# 5VProtect.net
KiCad netlist of a schematic drawn in Altium Designer
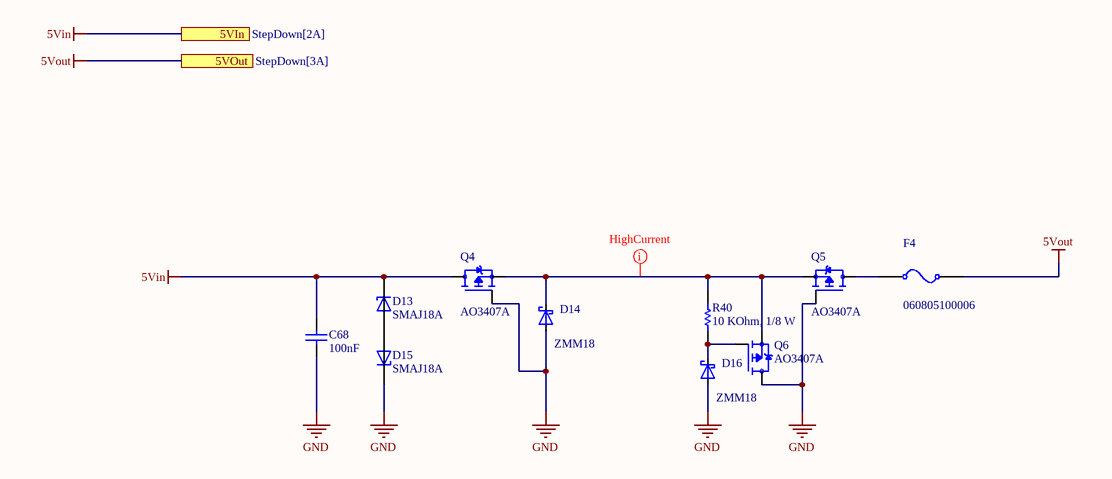
[diagram p0: 5VProtect.SchDoc]

(export (version "E")
  (design (tool "Eeschema 10.0.6"))
  (components
    (comp (ref "C68")
      (value "100nF")
      (footprint "CAP_0805")
      (description "CAP, size 0805, 0.1 nF, 50 VDC")
      (fields
        (field (name "TOLERANCE") "10%")
        (field (name "Comment") "0108051041050")
        (field (name "SOURCE") "Capacitor_0805_10_percent.SchLib")
      )
      (libsource (lib "Tin Tran") (part "0108056841050"))
    )
    (comp (ref "D13")
      (value "SMAJ18A")
      (footprint "DIOM4325X250N")
      (description "400W, 21.1V, 5%, Unidirectional, TVS")
      (fields (field (name "MF") "Taiwan Semiconductor"))
      (libsource (lib "Tin Tran") (part "SMAJ18A"))
    )
    (comp (ref "D14")
      (value "ZMM18")
      (footprint "SOD-80_MiniMELF_Glass")
      (libsource (lib "Tin Tran") (part "Schottky-Diode"))
    )
    (comp (ref "D15")
      (value "SMAJ18A")
      (footprint "DIOM4325X250N")
      (description "400W, 21.1V, 5%, Unidirectional, TVS")
      (fields (field (name "MF") "Taiwan Semiconductor"))
      (libsource (lib "Tin Tran") (part "SMAJ18A"))
    )
    (comp (ref "D16")
      (value "ZMM18")
      (footprint "SOD-80_MiniMELF_Glass")
      (libsource (lib "Tin Tran") (part "Schottky-Diode"))
    )
    (comp (ref "F4")
      (value "060805100006")
      (footprint "Fuse_SMD_0805")
      (description "Resettable Fuse, Size 0805, 6V, 1A")
      (fields (field (name "MANUFACTURER") "Littelfuse"))
      (libsource (lib "Tin Tran") (part "061812110016"))
    )
    (comp (ref "Q4")
      (value "AO3407A")
      (footprint "SOT95P280X125-3N")
      (description "P-Channel 30 V 4.3A (Ta) 1.4W (Ta) Surface Mount SOT-23-3")
      (fields (field (name "MF") "Alpha &"))
      (libsource (lib "Tin Tran") (part "AO3407A"))
    )
    (comp (ref "Q5")
      (value "AO3407A")
      (footprint "SOT95P280X125-3N")
      (description "P-Channel 30 V 4.3A (Ta) 1.4W (Ta) Surface Mount SOT-23-3")
      (fields (field (name "MF") "Alpha &"))
      (libsource (lib "Tin Tran") (part "AO3407A"))
    )
    (comp (ref "Q6")
      (value "AO3407A")
      (footprint "SOT95P280X125-3N")
      (description "P-Channel 30 V 4.3A (Ta) 1.4W (Ta) Surface Mount SOT-23-3")
      (fields (field (name "MF") "Alpha &"))
      (libsource (lib "Tin Tran") (part "AO3407A"))
    )
    (comp (ref "R40")
      (value "10 KOhm, 1/8 W")
      (footprint "RESISTOR_0805")
      (description "RES, size 0805, 10 KOhm, 1/8 W")
      (fields (field (name "Comment") "0008051031"))
      (libsource (lib "Tin Tran") (part "0008052035_1"))
    )
  )
  (nets
    (net (code "1") (name "5Vin") (class "Default")
      (node (ref "C68") (pin "2") (pinfunction "2_2") (pintype "passive"))
      (node (ref "D13") (pin "C") (pinfunction "C_C") (pintype "passive"))
      (node (ref "Q4") (pin "3") (pinfunction "D_3") (pintype "passive"))
    )
    (net (code "2") (name "5Vout") (class "Default")
      (node (ref "F4") (pin "1") (pinfunction "1_1") (pintype "passive"))
    )
    (net (code "3") (name "GND") (class "Default")
      (node (ref "C68") (pin "1") (pinfunction "1_1") (pintype "passive"))
      (node (ref "D14") (pin "A") (pinfunction "A_A") (pintype "passive"))
      (node (ref "D15") (pin "C") (pinfunction "C_C") (pintype "passive"))
      (node (ref "D16") (pin "A") (pinfunction "A_A") (pintype "passive"))
      (node (ref "Q4") (pin "1") (pinfunction "G_1") (pintype "passive"))
      (node (ref "Q5") (pin "1") (pinfunction "G_1") (pintype "passive"))
      (node (ref "Q6") (pin "3") (pinfunction "D_3") (pintype "passive"))
    )
    (net (code "4") (name "Net-(D13-PadA)") (class "Default")
      (node (ref "D13") (pin "A") (pinfunction "A_A") (pintype "passive"))
      (node (ref "D15") (pin "A") (pinfunction "A_A") (pintype "passive"))
    )
    (net (code "5") (name "Net-(Q4-S)") (class "Default")
      (node (ref "D14") (pin "K") (pinfunction "K_K") (pintype "passive"))
      (node (ref "Q4") (pin "2") (pinfunction "S_2") (pintype "passive"))
      (node (ref "Q5") (pin "2") (pinfunction "S_2") (pintype "passive"))
      (node (ref "Q6") (pin "2") (pinfunction "S_2") (pintype "passive"))
      (node (ref "R40") (pin "2") (pinfunction "2_2") (pintype "passive"))
    )
    (net (code "6") (name "Net-(Q5-D)") (class "Default")
      (node (ref "F4") (pin "0") (pinfunction "0_0") (pintype "passive"))
      (node (ref "Q5") (pin "3") (pinfunction "D_3") (pintype "passive"))
    )
    (net (code "7") (name "Net-(Q6-G)") (class "Default")
      (node (ref "D16") (pin "K") (pinfunction "K_K") (pintype "passive"))
      (node (ref "Q6") (pin "1") (pinfunction "G_1") (pintype "passive"))
      (node (ref "R40") (pin "1") (pinfunction "1_1") (pintype "passive"))
    )
  )
)
